# ProProject_20240815-UR5-__2024-08-29.net
KiCad netlist of a schematic drawn in EasyEDA Pro
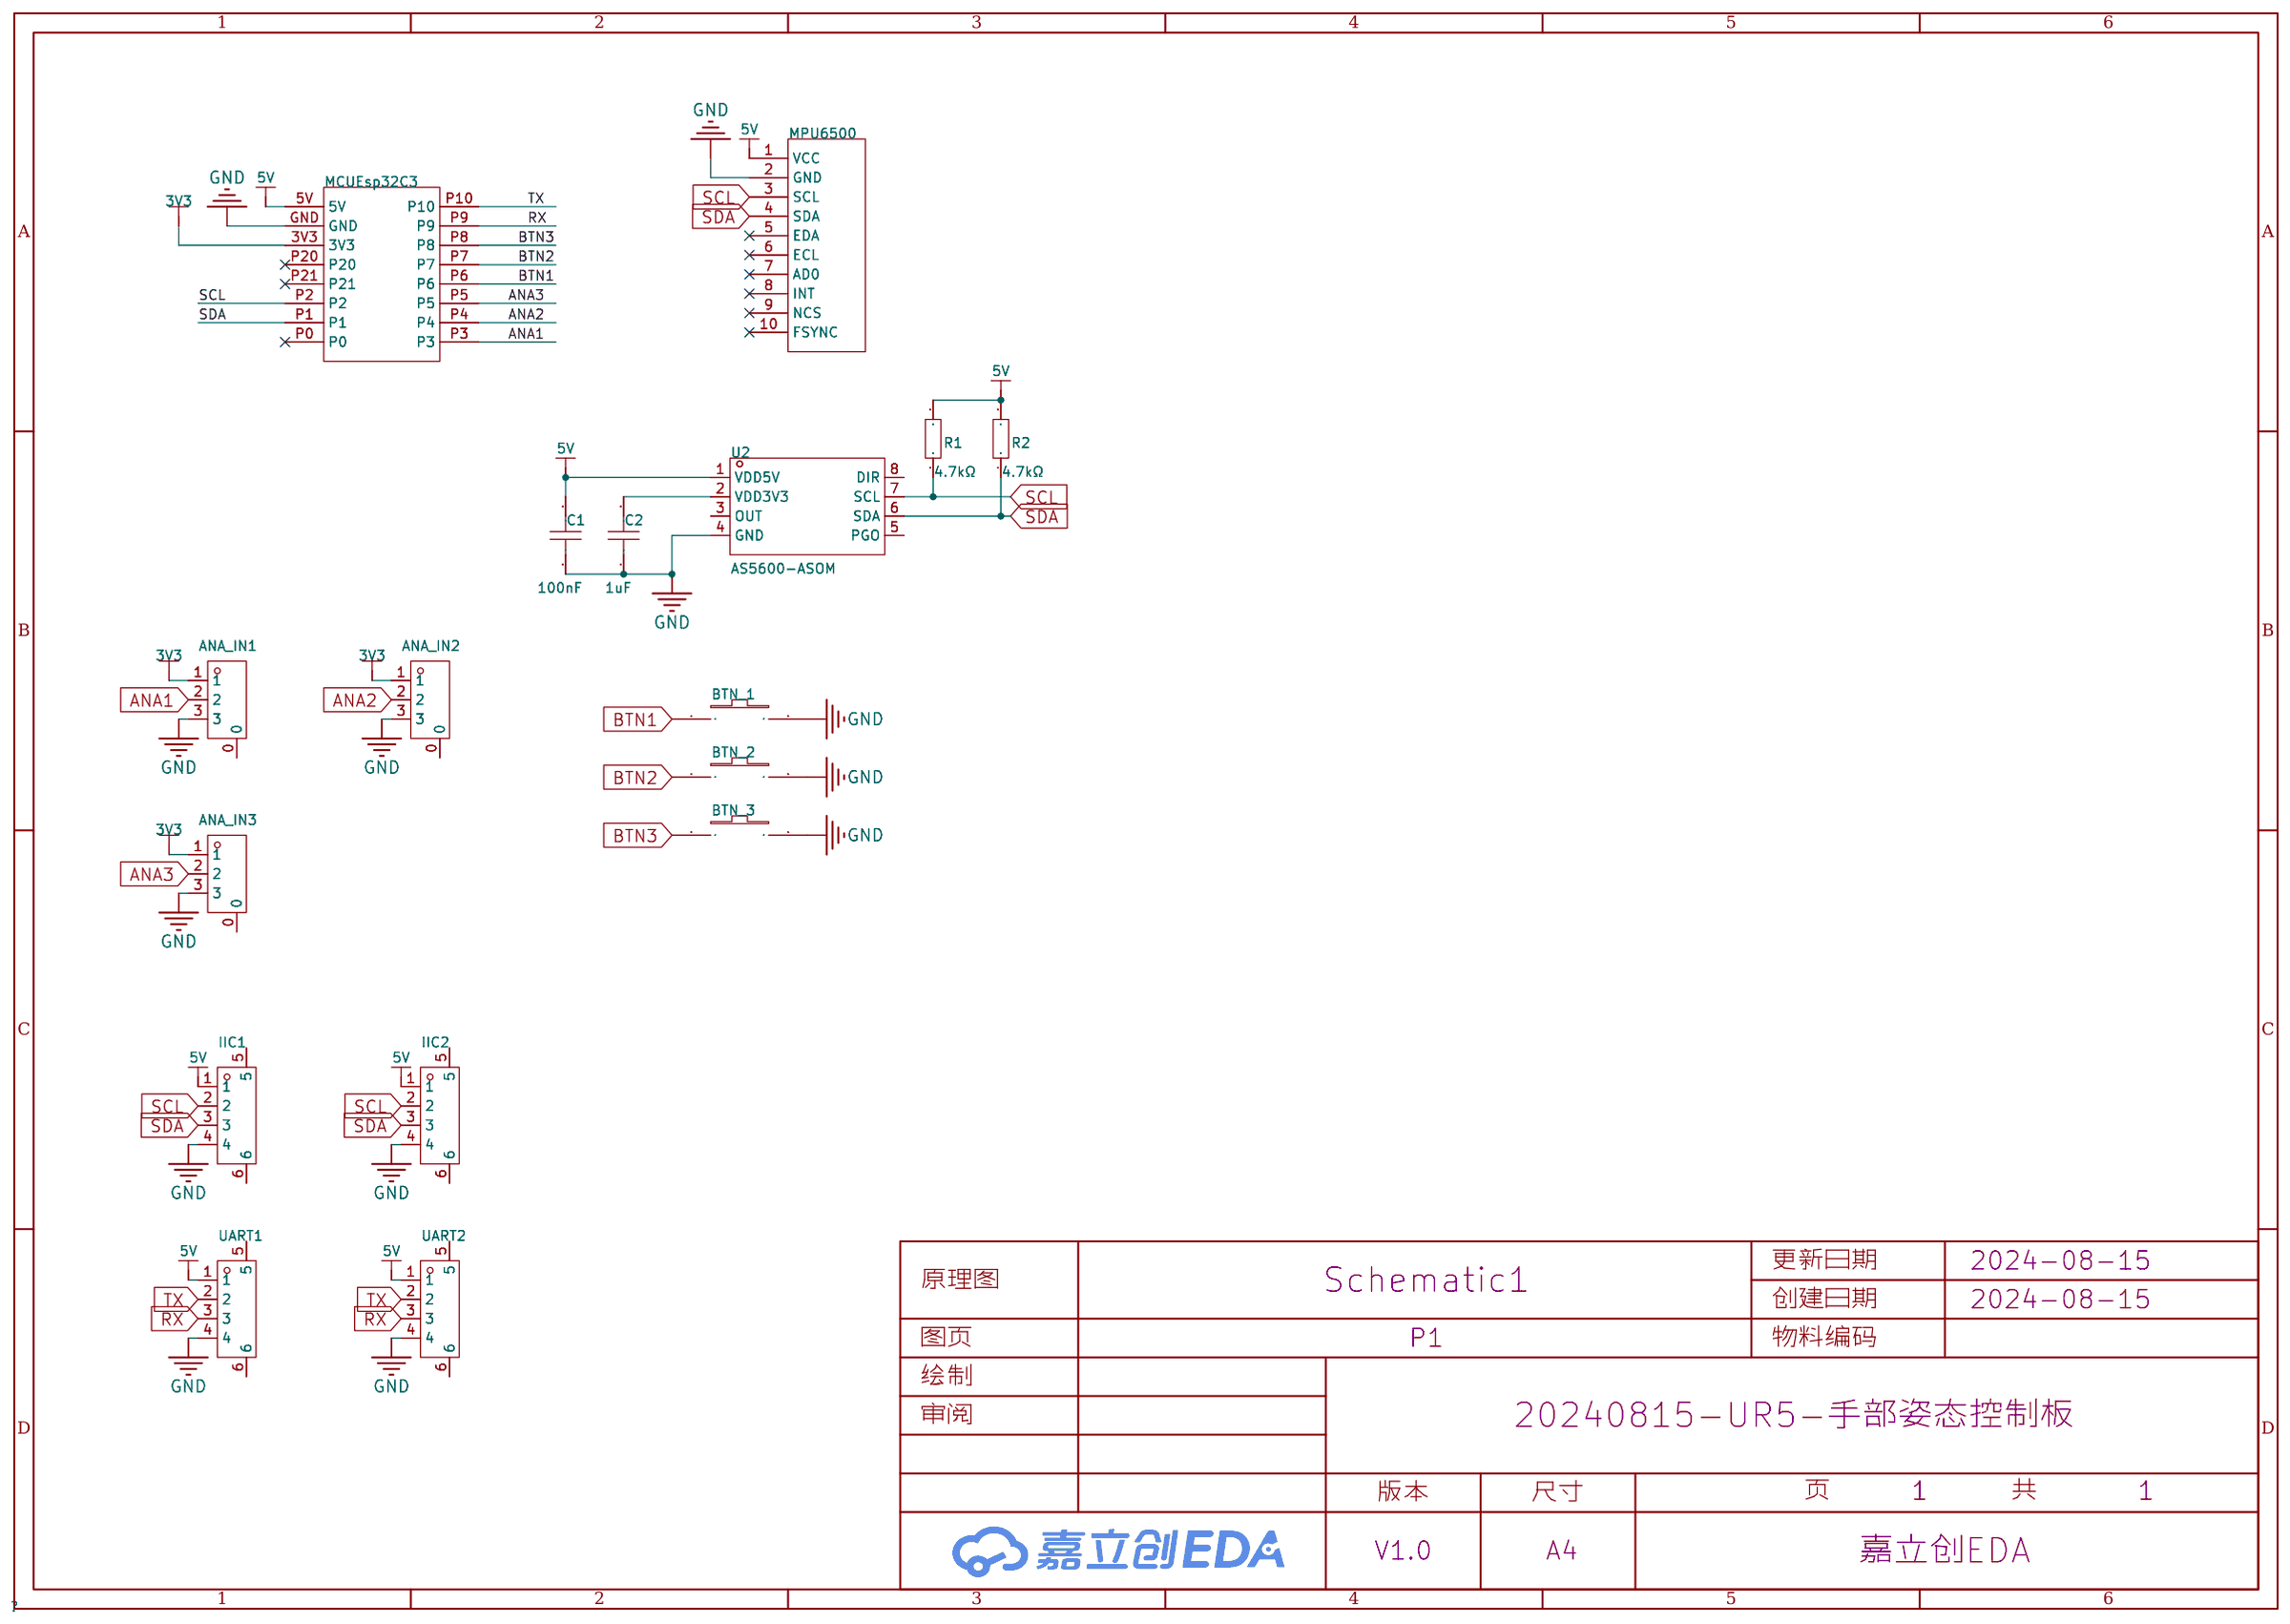
[diagram p0: schematic sheet]

(export (version "E")
  (design (tool "Eeschema 10.0.6"))
  (components
    (comp (ref "ANA_IN1")
      (value "SH1.0-3P")
      (footprint "easyedapro:CONN-SMD_3P-P1.00-L5.0-W5.0")
      (libsource (lib "easyedapro") (part "SH1.0-3P"))
    )
    (comp (ref "ANA_IN2")
      (value "SH1.0-3P")
      (footprint "easyedapro:CONN-SMD_3P-P1.00-L5.0-W5.0")
      (libsource (lib "easyedapro") (part "SH1.0-3P"))
    )
    (comp (ref "ANA_IN3")
      (value "SH1.0-3P")
      (footprint "easyedapro:CONN-SMD_3P-P1.00-L5.0-W5.0")
      (libsource (lib "easyedapro") (part "SH1.0-3P"))
    )
    (comp (ref "BTN_1")
      (value "K2-1104DZ-B4SW-04")
      (footprint "easyedapro:SW-TH_2P-L6.2-W6.2-P5.0")
      (description "作用力:250gf;安装方式:直插;开关长度:6mm;开关宽度:6mm;开关高度:4.5mm;触点电流:50mA;额定电压(DC):12V;绝缘电阻:100MΩ;机械寿命:10万次;")
      (fields (field (name "Manufacturer") "韩国韩荣"))
      (libsource (lib "easyedapro") (part "K2-1104DZ-B4SW-04"))
    )
    (comp (ref "BTN_2")
      (value "K2-1104DZ-B4SW-04")
      (footprint "easyedapro:SW-TH_2P-L6.2-W6.2-P5.0")
      (description "作用力:250gf;安装方式:直插;开关长度:6mm;开关宽度:6mm;开关高度:4.5mm;触点电流:50mA;额定电压(DC):12V;绝缘电阻:100MΩ;机械寿命:10万次;")
      (fields (field (name "Manufacturer") "韩国韩荣"))
      (libsource (lib "easyedapro") (part "K2-1104DZ-B4SW-04"))
    )
    (comp (ref "BTN_3")
      (value "K2-1104DZ-B4SW-04")
      (footprint "easyedapro:SW-TH_2P-L6.2-W6.2-P5.0")
      (description "作用力:250gf;安装方式:直插;开关长度:6mm;开关宽度:6mm;开关高度:4.5mm;触点电流:50mA;额定电压(DC):12V;绝缘电阻:100MΩ;机械寿命:10万次;")
      (fields (field (name "Manufacturer") "韩国韩荣"))
      (libsource (lib "easyedapro") (part "K2-1104DZ-B4SW-04"))
    )
    (comp (ref "C1")
      (value "1uF")
      (footprint "easyedapro:C1206")
      (description "容值:1uF;精度:±10%;额定电压:50V;材质(温度系数):X7R;")
      (fields
        (field (name "Manufacturer Part") "CL31B105KBHNNNE")
        (field (name "Manufacturer") "SAMSUNG(三星)")
      )
      (libsource (lib "easyedapro") (part "CL31B105KBHNNNE"))
    )
    (comp (ref "C2")
      (value "1uF")
      (footprint "easyedapro:C1206")
      (description "容值:1uF;精度:±10%;额定电压:50V;材质(温度系数):X7R;")
      (fields
        (field (name "Manufacturer Part") "CL31B105KBHNNNE")
        (field (name "Manufacturer") "SAMSUNG(三星)")
      )
      (libsource (lib "easyedapro") (part "CL31B105KBHNNNE"))
    )
    (comp (ref "IIC1")
      (value "SH1.0 4P")
      (footprint "easyedapro:CONN-SMD_4P-P1.00_C9900013908")
      (libsource (lib "easyedapro") (part "SH1.0 4P"))
    )
    (comp (ref "IIC2")
      (value "SH1.0 4P")
      (footprint "easyedapro:CONN-SMD_4P-P1.00_C9900013908")
      (libsource (lib "easyedapro") (part "SH1.0 4P"))
    )
    (comp (ref "MCUEsp32C3")
      (value "~")
      (footprint "easyedapro:Esp32-C3-mini")
      (libsource (lib "easyedapro") (part "Esp32-C3-mini"))
    )
    (comp (ref "MPU6500")
      (value "~")
      (footprint "easyedapro:6558模块")
      (libsource (lib "easyedapro") (part "MPU6500"))
    )
    (comp (ref "R1")
      (value "4.7kΩ")
      (footprint "easyedapro:R1206")
      (description "电阻类型:厚膜电阻;阻值:4.7kΩ;精度:±1%;功率:250mW;最大工作电压:200V;温度系数:±100ppm/°C;")
      (fields
        (field (name "Manufacturer Part") "1206W4F4701T5E")
        (field (name "Manufacturer") "UNI-ROYAL(厚声)")
      )
      (libsource (lib "easyedapro") (part "1206W4F4701T5E"))
    )
    (comp (ref "R2")
      (value "4.7kΩ")
      (footprint "easyedapro:R1206")
      (description "电阻类型:厚膜电阻;阻值:4.7kΩ;精度:±1%;功率:250mW;最大工作电压:200V;温度系数:±100ppm/°C;")
      (fields
        (field (name "Manufacturer Part") "1206W4F4701T5E")
        (field (name "Manufacturer") "UNI-ROYAL(厚声)")
      )
      (libsource (lib "easyedapro") (part "1206W4F4701T5E"))
    )
    (comp (ref "U2")
      (value "AS5600-ASOM")
      (footprint "easyedapro:SOIC-8_L5.0-W4.0-P1.27-LS6.0-BL")
      (description "旋转角度范围:0°~360°;")
      (fields (field (name "Manufacturer") "ams(艾迈斯半导体)"))
      (libsource (lib "easyedapro") (part "AS5600-ASOM"))
    )
    (comp (ref "UART1")
      (value "SH1.0 4P")
      (footprint "easyedapro:CONN-SMD_4P-P1.00_C9900013908")
      (libsource (lib "easyedapro") (part "SH1.0 4P"))
    )
    (comp (ref "UART2")
      (value "SH1.0 4P")
      (footprint "easyedapro:CONN-SMD_4P-P1.00_C9900013908")
      (libsource (lib "easyedapro") (part "SH1.0 4P"))
    )
  )
  (nets
    (net (code "1") (name "3V3") (class "Default")
      (node (ref "ANA_IN1") (pin "1") (pinfunction "1_1") (pintype "unspecified"))
      (node (ref "ANA_IN2") (pin "1") (pinfunction "1_1") (pintype "unspecified"))
      (node (ref "ANA_IN3") (pin "1") (pinfunction "1_1") (pintype "unspecified"))
      (node (ref "MCUEsp32C3") (pin "3V3") (pinfunction "3V3_3V3") (pintype "output"))
    )
    (net (code "2") (name "5V") (class "Default")
      (node (ref "C1") (pin "2") (pinfunction "2_2") (pintype "unspecified"))
      (node (ref "IIC1") (pin "1") (pinfunction "1_1") (pintype "unspecified"))
      (node (ref "IIC2") (pin "1") (pinfunction "1_1") (pintype "unspecified"))
      (node (ref "MCUEsp32C3") (pin "5V") (pinfunction "5V_5V") (pintype "input"))
      (node (ref "MPU6500") (pin "1") (pinfunction "VCC_1") (pintype "input"))
      (node (ref "R1") (pin "2") (pinfunction "2_2") (pintype "input"))
      (node (ref "R2") (pin "2") (pinfunction "2_2") (pintype "input"))
      (node (ref "U2") (pin "1") (pinfunction "VDD5V_1") (pintype "input"))
      (node (ref "UART1") (pin "1") (pinfunction "1_1") (pintype "unspecified"))
      (node (ref "UART2") (pin "1") (pinfunction "1_1") (pintype "unspecified"))
    )
    (net (code "3") (name "ANA1") (class "Default")
      (node (ref "ANA_IN1") (pin "2") (pinfunction "2_2") (pintype "unspecified"))
      (node (ref "MCUEsp32C3") (pin "P3") (pinfunction "P3_P3") (pintype "bidirectional"))
    )
    (net (code "4") (name "ANA2") (class "Default")
      (node (ref "ANA_IN2") (pin "2") (pinfunction "2_2") (pintype "unspecified"))
      (node (ref "MCUEsp32C3") (pin "P4") (pinfunction "P4_P4") (pintype "bidirectional"))
    )
    (net (code "5") (name "ANA3") (class "Default")
      (node (ref "ANA_IN3") (pin "2") (pinfunction "2_2") (pintype "unspecified"))
      (node (ref "MCUEsp32C3") (pin "P5") (pinfunction "P5_P5") (pintype "bidirectional"))
    )
    (net (code "6") (name "BTN1") (class "Default")
      (node (ref "BTN_1") (pin "1") (pinfunction "1_1") (pintype "input"))
      (node (ref "MCUEsp32C3") (pin "P6") (pinfunction "P6_P6") (pintype "bidirectional"))
    )
    (net (code "7") (name "BTN2") (class "Default")
      (node (ref "BTN_2") (pin "1") (pinfunction "1_1") (pintype "input"))
      (node (ref "MCUEsp32C3") (pin "P7") (pinfunction "P7_P7") (pintype "bidirectional"))
    )
    (net (code "8") (name "BTN3") (class "Default")
      (node (ref "BTN_3") (pin "1") (pinfunction "1_1") (pintype "input"))
      (node (ref "MCUEsp32C3") (pin "P8") (pinfunction "P8_P8") (pintype "bidirectional"))
    )
    (net (code "9") (name "GND") (class "Default")
      (node (ref "ANA_IN1") (pin "3") (pinfunction "3_3") (pintype "unspecified"))
      (node (ref "ANA_IN2") (pin "3") (pinfunction "3_3") (pintype "unspecified"))
      (node (ref "ANA_IN3") (pin "3") (pinfunction "3_3") (pintype "unspecified"))
      (node (ref "BTN_1") (pin "2") (pinfunction "2_2") (pintype "input"))
      (node (ref "BTN_2") (pin "2") (pinfunction "2_2") (pintype "input"))
      (node (ref "BTN_3") (pin "2") (pinfunction "2_2") (pintype "input"))
      (node (ref "C1") (pin "1") (pinfunction "1_1") (pintype "unspecified"))
      (node (ref "C2") (pin "1") (pinfunction "1_1") (pintype "unspecified"))
      (node (ref "IIC1") (pin "4") (pinfunction "4_4") (pintype "unspecified"))
      (node (ref "IIC2") (pin "4") (pinfunction "4_4") (pintype "unspecified"))
      (node (ref "MCUEsp32C3") (pin "GND") (pinfunction "GND_GND") (pintype "input"))
      (node (ref "MPU6500") (pin "2") (pinfunction "GND_2") (pintype "input"))
      (node (ref "U2") (pin "4") (pinfunction "GND_4") (pintype "input"))
      (node (ref "UART1") (pin "4") (pinfunction "4_4") (pintype "unspecified"))
      (node (ref "UART2") (pin "4") (pinfunction "4_4") (pintype "unspecified"))
    )
    (net (code "10") (name "Net-(U2-VDD3V3)") (class "Default")
      (node (ref "C2") (pin "2") (pinfunction "2_2") (pintype "unspecified"))
      (node (ref "U2") (pin "2") (pinfunction "VDD3V3_2") (pintype "input"))
    )
    (net (code "11") (name "RX") (class "Default")
      (node (ref "MCUEsp32C3") (pin "P9") (pinfunction "P9_P9") (pintype "bidirectional"))
      (node (ref "UART1") (pin "3") (pinfunction "3_3") (pintype "unspecified"))
      (node (ref "UART2") (pin "3") (pinfunction "3_3") (pintype "unspecified"))
    )
    (net (code "12") (name "SCL") (class "Default")
      (node (ref "IIC1") (pin "2") (pinfunction "2_2") (pintype "unspecified"))
      (node (ref "IIC2") (pin "2") (pinfunction "2_2") (pintype "unspecified"))
      (node (ref "MCUEsp32C3") (pin "P2") (pinfunction "P2_P2") (pintype "bidirectional"))
      (node (ref "MPU6500") (pin "3") (pinfunction "SCL_3") (pintype "input"))
      (node (ref "R1") (pin "1") (pinfunction "1_1") (pintype "input"))
      (node (ref "U2") (pin "7") (pinfunction "SCL_7") (pintype "input"))
    )
    (net (code "13") (name "SDA") (class "Default")
      (node (ref "IIC1") (pin "3") (pinfunction "3_3") (pintype "unspecified"))
      (node (ref "IIC2") (pin "3") (pinfunction "3_3") (pintype "unspecified"))
      (node (ref "MCUEsp32C3") (pin "P1") (pinfunction "P1_P1") (pintype "bidirectional"))
      (node (ref "MPU6500") (pin "4") (pinfunction "SDA_4") (pintype "input"))
      (node (ref "R2") (pin "1") (pinfunction "1_1") (pintype "input"))
      (node (ref "U2") (pin "6") (pinfunction "SDA_6") (pintype "input"))
    )
    (net (code "14") (name "TX") (class "Default")
      (node (ref "MCUEsp32C3") (pin "P10") (pinfunction "P10_P10") (pintype "bidirectional"))
      (node (ref "UART1") (pin "2") (pinfunction "2_2") (pintype "unspecified"))
      (node (ref "UART2") (pin "2") (pinfunction "2_2") (pintype "unspecified"))
    )
    (net (code "15") (name "unconnected-(ANA_IN1-Pad0)") (class "Default")
      (node (ref "ANA_IN1") (pin "0") (pinfunction "0_0") (pintype "unspecified"))
    )
    (net (code "16") (name "unconnected-(ANA_IN2-Pad0)") (class "Default")
      (node (ref "ANA_IN2") (pin "0") (pinfunction "0_0") (pintype "unspecified"))
    )
    (net (code "17") (name "unconnected-(ANA_IN3-Pad0)") (class "Default")
      (node (ref "ANA_IN3") (pin "0") (pinfunction "0_0") (pintype "unspecified"))
    )
    (net (code "18") (name "unconnected-(IIC1-Pad5)") (class "Default")
      (node (ref "IIC1") (pin "5") (pinfunction "5_5") (pintype "unspecified"))
    )
    (net (code "19") (name "unconnected-(IIC1-Pad6)") (class "Default")
      (node (ref "IIC1") (pin "6") (pinfunction "6_6") (pintype "unspecified"))
    )
    (net (code "20") (name "unconnected-(IIC2-Pad5)") (class "Default")
      (node (ref "IIC2") (pin "5") (pinfunction "5_5") (pintype "unspecified"))
    )
    (net (code "21") (name "unconnected-(IIC2-Pad6)") (class "Default")
      (node (ref "IIC2") (pin "6") (pinfunction "6_6") (pintype "unspecified"))
    )
    (net (code "22") (name "unconnected-(MCUEsp32C3-PadP0)") (class "Default")
      (node (ref "MCUEsp32C3") (pin "P0") (pinfunction "P0_P0") (pintype "bidirectional+no_connect"))
    )
    (net (code "23") (name "unconnected-(MCUEsp32C3-PadP20)") (class "Default")
      (node (ref "MCUEsp32C3") (pin "P20") (pinfunction "P20_P20") (pintype "bidirectional+no_connect"))
    )
    (net (code "24") (name "unconnected-(MCUEsp32C3-PadP21)") (class "Default")
      (node (ref "MCUEsp32C3") (pin "P21") (pinfunction "P21_P21") (pintype "bidirectional+no_connect"))
    )
    (net (code "25") (name "unconnected-(MPU6500-AD0-Pad7)") (class "Default")
      (node (ref "MPU6500") (pin "7") (pinfunction "AD0_7") (pintype "input+no_connect"))
    )
    (net (code "26") (name "unconnected-(MPU6500-ECL-Pad6)") (class "Default")
      (node (ref "MPU6500") (pin "6") (pinfunction "ECL_6") (pintype "input+no_connect"))
    )
    (net (code "27") (name "unconnected-(MPU6500-EDA-Pad5)") (class "Default")
      (node (ref "MPU6500") (pin "5") (pinfunction "EDA_5") (pintype "input+no_connect"))
    )
    (net (code "28") (name "unconnected-(MPU6500-FSYNC-Pad10)") (class "Default")
      (node (ref "MPU6500") (pin "10") (pinfunction "FSYNC_10") (pintype "input+no_connect"))
    )
    (net (code "29") (name "unconnected-(MPU6500-INT-Pad8)") (class "Default")
      (node (ref "MPU6500") (pin "8") (pinfunction "INT_8") (pintype "input+no_connect"))
    )
    (net (code "30") (name "unconnected-(MPU6500-NCS-Pad9)") (class "Default")
      (node (ref "MPU6500") (pin "9") (pinfunction "NCS_9") (pintype "input+no_connect"))
    )
    (net (code "31") (name "unconnected-(U2-DIR-Pad8)") (class "Default")
      (node (ref "U2") (pin "8") (pinfunction "DIR_8") (pintype "input"))
    )
    (net (code "32") (name "unconnected-(U2-OUT-Pad3)") (class "Default")
      (node (ref "U2") (pin "3") (pinfunction "OUT_3") (pintype "input"))
    )
    (net (code "33") (name "unconnected-(U2-PGO-Pad5)") (class "Default")
      (node (ref "U2") (pin "5") (pinfunction "PGO_5") (pintype "input"))
    )
    (net (code "34") (name "unconnected-(UART1-Pad5)") (class "Default")
      (node (ref "UART1") (pin "5") (pinfunction "5_5") (pintype "unspecified"))
    )
    (net (code "35") (name "unconnected-(UART1-Pad6)") (class "Default")
      (node (ref "UART1") (pin "6") (pinfunction "6_6") (pintype "unspecified"))
    )
    (net (code "36") (name "unconnected-(UART2-Pad5)") (class "Default")
      (node (ref "UART2") (pin "5") (pinfunction "5_5") (pintype "unspecified"))
    )
    (net (code "37") (name "unconnected-(UART2-Pad6)") (class "Default")
      (node (ref "UART2") (pin "6") (pinfunction "6_6") (pintype "unspecified"))
    )
  )
)
